# board.net
KiCad netlist of a schematic drawn in EAGLE
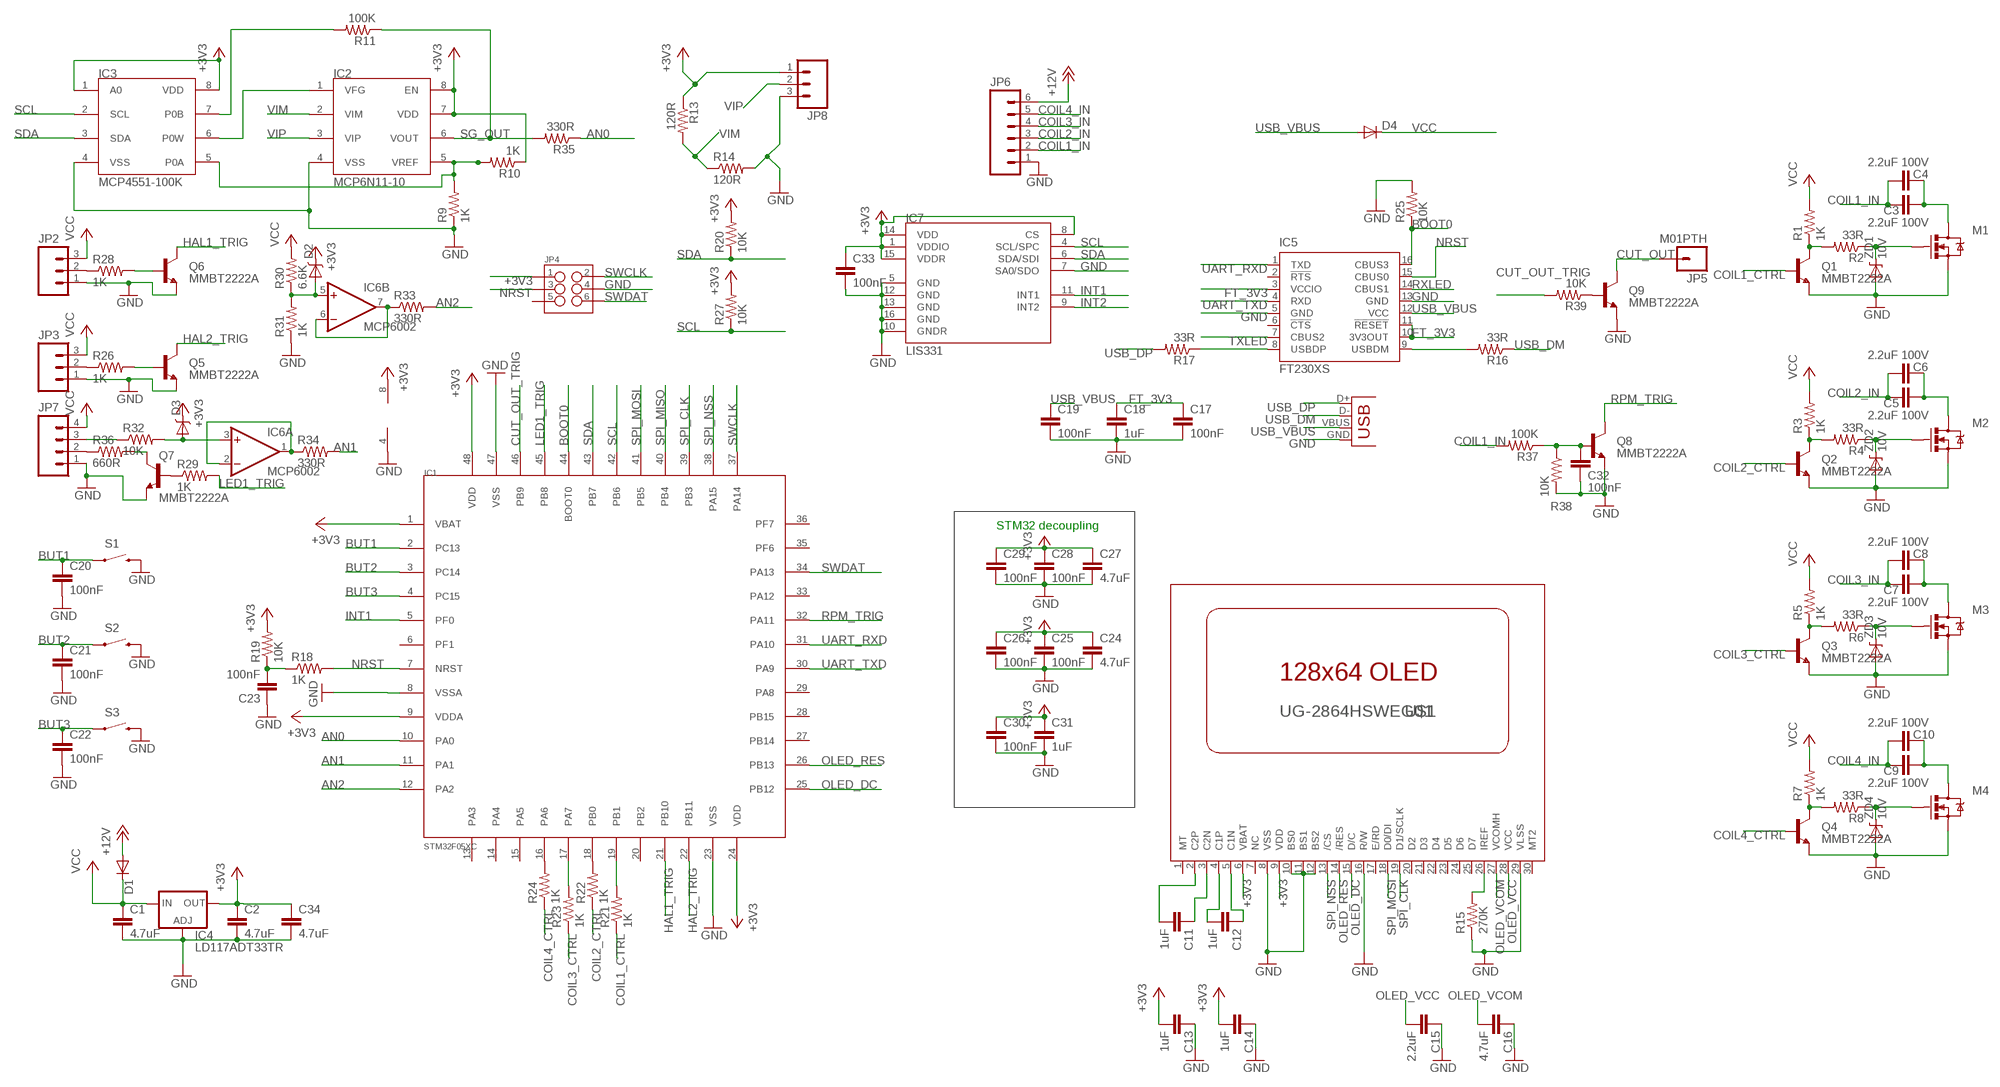
[diagram p0: schematic, sheet 1]

(export (version "E")
  (design (tool "Eeschema 10.0.6"))
  (components
    (comp (ref "C1")
      (value "4.7uF")
      (footprint "eagle-import:0603-CAP")
      (libsource (lib "eagle-import") (part "SparkFun-Passives_CAP0603-CAP"))
    )
    (comp (ref "C2")
      (value "4.7uF")
      (footprint "eagle-import:0603-CAP")
      (libsource (lib "eagle-import") (part "SparkFun-Passives_CAP0603-CAP"))
    )
    (comp (ref "C3")
      (value "2.2uF 100V")
      (footprint "eagle-import:1206")
      (libsource (lib "eagle-import") (part "2.2UF-CERCAP-10009"))
    )
    (comp (ref "C4")
      (value "2.2uF 100V")
      (footprint "eagle-import:1206")
      (libsource (lib "eagle-import") (part "2.2UF-CERCAP-10009"))
    )
    (comp (ref "C5")
      (value "2.2uF 100V")
      (footprint "eagle-import:1206")
      (libsource (lib "eagle-import") (part "2.2UF-CERCAP-10009"))
    )
    (comp (ref "C6")
      (value "2.2uF 100V")
      (footprint "eagle-import:1206")
      (libsource (lib "eagle-import") (part "2.2UF-CERCAP-10009"))
    )
    (comp (ref "C7")
      (value "2.2uF 100V")
      (footprint "eagle-import:1206")
      (libsource (lib "eagle-import") (part "2.2UF-CERCAP-10009"))
    )
    (comp (ref "C8")
      (value "2.2uF 100V")
      (footprint "eagle-import:1206")
      (libsource (lib "eagle-import") (part "2.2UF-CERCAP-10009"))
    )
    (comp (ref "C9")
      (value "2.2uF 100V")
      (footprint "eagle-import:1206")
      (libsource (lib "eagle-import") (part "2.2UF-CERCAP-10009"))
    )
    (comp (ref "C10")
      (value "2.2uF 100V")
      (footprint "eagle-import:1206")
      (libsource (lib "eagle-import") (part "2.2UF-CERCAP-10009"))
    )
    (comp (ref "C11")
      (value "1uF")
      (footprint "eagle-import:0603-CAP")
      (libsource (lib "eagle-import") (part "CAP0603-CAP"))
    )
    (comp (ref "C12")
      (value "1uF")
      (footprint "eagle-import:0603-CAP")
      (libsource (lib "eagle-import") (part "CAP0603-CAP"))
    )
    (comp (ref "C13")
      (value "1uF")
      (footprint "eagle-import:0603-CAP")
      (libsource (lib "eagle-import") (part "CAP0603-CAP"))
    )
    (comp (ref "C14")
      (value "1uF")
      (footprint "eagle-import:0603-CAP")
      (libsource (lib "eagle-import") (part "CAP0603-CAP"))
    )
    (comp (ref "C15")
      (value "2.2uF")
      (footprint "eagle-import:0603-CAP")
      (libsource (lib "eagle-import") (part "CAP0603-CAP"))
    )
    (comp (ref "C16")
      (value "4.7uF")
      (footprint "eagle-import:0603-CAP")
      (libsource (lib "eagle-import") (part "CAP0603-CAP"))
    )
    (comp (ref "C17")
      (value "100nF")
      (footprint "eagle-import:0603-CAP")
      (libsource (lib "eagle-import") (part "CAP0603-CAP"))
    )
    (comp (ref "C18")
      (value "1uF")
      (footprint "eagle-import:0603-CAP")
      (libsource (lib "eagle-import") (part "CAP0603-CAP"))
    )
    (comp (ref "C19")
      (value "100nF")
      (footprint "eagle-import:0603-CAP")
      (libsource (lib "eagle-import") (part "CAP0603-CAP"))
    )
    (comp (ref "C20")
      (value "100nF")
      (footprint "eagle-import:0603-CAP")
      (libsource (lib "eagle-import") (part "CAP0603-CAP"))
    )
    (comp (ref "C21")
      (value "100nF")
      (footprint "eagle-import:0603-CAP")
      (libsource (lib "eagle-import") (part "CAP0603-CAP"))
    )
    (comp (ref "C22")
      (value "100nF")
      (footprint "eagle-import:0603-CAP")
      (libsource (lib "eagle-import") (part "CAP0603-CAP"))
    )
    (comp (ref "C23")
      (value "100nF")
      (footprint "eagle-import:0603-CAP")
      (libsource (lib "eagle-import") (part "CAP0603-CAP"))
    )
    (comp (ref "C24")
      (value "4.7uF")
      (footprint "eagle-import:0603-CAP")
      (libsource (lib "eagle-import") (part "SparkFun-Passives_CAP0603-CAP"))
    )
    (comp (ref "C25")
      (value "100nF")
      (footprint "eagle-import:0603-CAP")
      (libsource (lib "eagle-import") (part "CAP0603-CAP"))
    )
    (comp (ref "C26")
      (value "100nF")
      (footprint "eagle-import:0603-CAP")
      (libsource (lib "eagle-import") (part "CAP0603-CAP"))
    )
    (comp (ref "C27")
      (value "4.7uF")
      (footprint "eagle-import:0603-CAP")
      (libsource (lib "eagle-import") (part "SparkFun-Passives_CAP0603-CAP"))
    )
    (comp (ref "C28")
      (value "100nF")
      (footprint "eagle-import:0603-CAP")
      (libsource (lib "eagle-import") (part "CAP0603-CAP"))
    )
    (comp (ref "C29")
      (value "100nF")
      (footprint "eagle-import:0603-CAP")
      (libsource (lib "eagle-import") (part "CAP0603-CAP"))
    )
    (comp (ref "C30")
      (value "100nF")
      (footprint "eagle-import:0603-CAP")
      (libsource (lib "eagle-import") (part "CAP0603-CAP"))
    )
    (comp (ref "C31")
      (value "1uF")
      (footprint "eagle-import:0603-CAP")
      (libsource (lib "eagle-import") (part "CAP0603-CAP"))
    )
    (comp (ref "C32")
      (value "100nF")
      (footprint "eagle-import:0603-CAP")
      (libsource (lib "eagle-import") (part "CAP0603-CAP"))
    )
    (comp (ref "C33")
      (value "100nF")
      (footprint "eagle-import:0603-CAP")
      (libsource (lib "eagle-import") (part "CAP0603-CAP"))
    )
    (comp (ref "C34")
      (value "4.7uF")
      (footprint "eagle-import:0603-CAP")
      (libsource (lib "eagle-import") (part "SparkFun-Passives_CAP0603-CAP"))
    )
    (comp (ref "D1")
      (value "DIODESMA")
      (footprint "eagle-import:SMA-DIODE")
      (libsource (lib "eagle-import") (part "DIODESMA"))
    )
    (comp (ref "D2")
      (value "BAT20JFILM")
      (footprint "eagle-import:SOD-323")
      (libsource (lib "eagle-import") (part "BAT20JFILM"))
    )
    (comp (ref "D3")
      (value "BAT20JFILM")
      (footprint "eagle-import:SOD-323")
      (libsource (lib "eagle-import") (part "BAT20JFILM"))
    )
    (comp (ref "D4")
      (value "DIODESMA")
      (footprint "eagle-import:SMA-DIODE")
      (libsource (lib "eagle-import") (part "DIODESMA"))
    )
    (comp (ref "IC1")
      (value "STM32F05XC")
      (footprint "eagle-import:LQFP-48")
      (libsource (lib "eagle-import") (part "STM32F05XC"))
    )
    (comp (ref "IC2")
      (value "MCP6N11-10")
      (footprint "eagle-import:SO08")
      (libsource (lib "eagle-import") (part "MCP6N11"))
    )
    (comp (ref "IC3")
      (value "MCP4551-100K")
      (footprint "eagle-import:MSOP-8")
      (libsource (lib "eagle-import") (part "MCP45X1"))
    )
    (comp (ref "IC4")
      (value "LD117ADT33TR")
      (footprint "eagle-import:DPACK")
      (libsource (lib "eagle-import") (part "LD117A?DT33TR"))
    )
    (comp (ref "IC5")
      (value "FT230XS")
      (footprint "eagle-import:SSOP16")
      (libsource (lib "eagle-import") (part "FT230XS"))
    )
    (comp (ref "IC6")
      (value "MCP6002")
      (footprint "eagle-import:SO08")
      (libsource (lib "eagle-import") (part "TL072D"))
    )
    (comp (ref "IC7")
      (value "LIS331")
      (footprint "eagle-import:LGA16-3MM")
      (libsource (lib "eagle-import") (part "LIS331"))
    )
    (comp (ref "JP1")
      (value "USBSMD")
      (footprint "eagle-import:USB-MINIB")
      (libsource (lib "eagle-import") (part "USBSMD"))
    )
    (comp (ref "JP2")
      (value "M03PTH")
      (footprint "eagle-import:1X03")
      (libsource (lib "eagle-import") (part "M03PTH"))
    )
    (comp (ref "JP3")
      (value "M03PTH")
      (footprint "eagle-import:1X03")
      (libsource (lib "eagle-import") (part "M03PTH"))
    )
    (comp (ref "JP4")
      (value "M03X22X3_SILK_SM")
      (footprint "eagle-import:2X3")
      (libsource (lib "eagle-import") (part "M03X22X3_SILK_SM"))
    )
    (comp (ref "JP5")
      (value "M01PTH")
      (footprint "eagle-import:1X01")
      (libsource (lib "eagle-import") (part "M01PTH"))
    )
    (comp (ref "JP6")
      (value "M063.5MM-6")
      (footprint "eagle-import:SCREWTERMINAL-3.5MM-6")
      (libsource (lib "eagle-import") (part "M063.5MM-6"))
    )
    (comp (ref "JP7")
      (value "M04PTH")
      (footprint "eagle-import:1X04")
      (libsource (lib "eagle-import") (part "M04PTH"))
    )
    (comp (ref "JP8")
      (value "M03PTH")
      (footprint "eagle-import:1X03")
      (libsource (lib "eagle-import") (part "M03PTH"))
    )
    (comp (ref "M1")
      (value "MOSFET-NCHANNELFDD8580")
      (footprint "eagle-import:DPAK")
      (libsource (lib "eagle-import") (part "MOSFET-NCHANNELFDD8580"))
    )
    (comp (ref "M2")
      (value "MOSFET-NCHANNELFDD8580")
      (footprint "eagle-import:DPAK")
      (libsource (lib "eagle-import") (part "MOSFET-NCHANNELFDD8580"))
    )
    (comp (ref "M3")
      (value "MOSFET-NCHANNELFDD8580")
      (footprint "eagle-import:DPAK")
      (libsource (lib "eagle-import") (part "MOSFET-NCHANNELFDD8580"))
    )
    (comp (ref "M4")
      (value "MOSFET-NCHANNELFDD8580")
      (footprint "eagle-import:DPAK")
      (libsource (lib "eagle-import") (part "MOSFET-NCHANNELFDD8580"))
    )
    (comp (ref "Q1")
      (value "MMBT2222A")
      (footprint "eagle-import:SOT23")
      (libsource (lib "eagle-import") (part "TRANSISTOR_NPNMMBT2222A"))
    )
    (comp (ref "Q2")
      (value "MMBT2222A")
      (footprint "eagle-import:SOT23")
      (libsource (lib "eagle-import") (part "TRANSISTOR_NPNMMBT2222A"))
    )
    (comp (ref "Q3")
      (value "MMBT2222A")
      (footprint "eagle-import:SOT23")
      (libsource (lib "eagle-import") (part "TRANSISTOR_NPNMMBT2222A"))
    )
    (comp (ref "Q4")
      (value "MMBT2222A")
      (footprint "eagle-import:SOT23")
      (libsource (lib "eagle-import") (part "TRANSISTOR_NPNMMBT2222A"))
    )
    (comp (ref "Q5")
      (value "MMBT2222A")
      (footprint "eagle-import:SOT23")
      (fields (field (name "PROD_ID") "TRANS-08049"))
      (libsource (lib "eagle-import") (part "TRANSISTOR_NPNMMBT2222A"))
    )
    (comp (ref "Q6")
      (value "MMBT2222A")
      (footprint "eagle-import:SOT23")
      (fields (field (name "PROD_ID") "TRANS-08049"))
      (libsource (lib "eagle-import") (part "TRANSISTOR_NPNMMBT2222A"))
    )
    (comp (ref "Q7")
      (value "MMBT2222A")
      (footprint "eagle-import:SOT23")
      (libsource (lib "eagle-import") (part "TRANSISTOR_NPNMMBT2222A"))
    )
    (comp (ref "Q8")
      (value "MMBT2222A")
      (footprint "eagle-import:SOT23")
      (libsource (lib "eagle-import") (part "TRANSISTOR_NPNMMBT2222A"))
    )
    (comp (ref "Q9")
      (value "MMBT2222A")
      (footprint "eagle-import:SOT23")
      (libsource (lib "eagle-import") (part "TRANSISTOR_NPNMMBT2222A"))
    )
    (comp (ref "R1")
      (value "1K")
      (footprint "eagle-import:0603-RES")
      (libsource (lib "eagle-import") (part "RESISTOR0603-RES"))
    )
    (comp (ref "R2")
      (value "33R")
      (footprint "eagle-import:0603-RES")
      (libsource (lib "eagle-import") (part "RESISTOR0603-RES"))
    )
    (comp (ref "R3")
      (value "1K")
      (footprint "eagle-import:0603-RES")
      (libsource (lib "eagle-import") (part "RESISTOR0603-RES"))
    )
    (comp (ref "R4")
      (value "33R")
      (footprint "eagle-import:0603-RES")
      (libsource (lib "eagle-import") (part "RESISTOR0603-RES"))
    )
    (comp (ref "R5")
      (value "1K")
      (footprint "eagle-import:0603-RES")
      (libsource (lib "eagle-import") (part "RESISTOR0603-RES"))
    )
    (comp (ref "R6")
      (value "33R")
      (footprint "eagle-import:0603-RES")
      (libsource (lib "eagle-import") (part "RESISTOR0603-RES"))
    )
    (comp (ref "R7")
      (value "1K")
      (footprint "eagle-import:0603-RES")
      (libsource (lib "eagle-import") (part "RESISTOR0603-RES"))
    )
    (comp (ref "R8")
      (value "33R")
      (footprint "eagle-import:0603-RES")
      (libsource (lib "eagle-import") (part "RESISTOR0603-RES"))
    )
    (comp (ref "R9")
      (value "1K")
      (footprint "eagle-import:0603-RES")
      (libsource (lib "eagle-import") (part "RESISTOR0603-RES"))
    )
    (comp (ref "R10")
      (value "1K")
      (footprint "eagle-import:0603-RES")
      (libsource (lib "eagle-import") (part "RESISTOR0603-RES"))
    )
    (comp (ref "R11")
      (value "100K")
      (footprint "eagle-import:0603-RES")
      (libsource (lib "eagle-import") (part "RESISTOR0603-RES"))
    )
    (comp (ref "R13")
      (value "120R")
      (footprint "eagle-import:0603-RES")
      (libsource (lib "eagle-import") (part "RESISTOR0603-RES"))
    )
    (comp (ref "R14")
      (value "120R")
      (footprint "eagle-import:0603-RES")
      (libsource (lib "eagle-import") (part "RESISTOR0603-RES"))
    )
    (comp (ref "R15")
      (value "270K")
      (footprint "eagle-import:0603-RES")
      (libsource (lib "eagle-import") (part "RESISTOR0603"))
    )
    (comp (ref "R16")
      (value "33R")
      (footprint "eagle-import:0603-RES")
      (libsource (lib "eagle-import") (part "RESISTOR0603-RES"))
    )
    (comp (ref "R17")
      (value "33R")
      (footprint "eagle-import:0603-RES")
      (libsource (lib "eagle-import") (part "RESISTOR0603-RES"))
    )
    (comp (ref "R18")
      (value "1K")
      (footprint "eagle-import:0603-RES")
      (libsource (lib "eagle-import") (part "RESISTOR0603-RES"))
    )
    (comp (ref "R19")
      (value "10K")
      (footprint "eagle-import:0603-RES")
      (libsource (lib "eagle-import") (part "RESISTOR0603-RES"))
    )
    (comp (ref "R20")
      (value "10K")
      (footprint "eagle-import:0603-RES")
      (libsource (lib "eagle-import") (part "RESISTOR0603-RES"))
    )
    (comp (ref "R21")
      (value "1K")
      (footprint "eagle-import:0603-RES")
      (libsource (lib "eagle-import") (part "RESISTOR0603-RES"))
    )
    (comp (ref "R22")
      (value "1K")
      (footprint "eagle-import:0603-RES")
      (libsource (lib "eagle-import") (part "RESISTOR0603-RES"))
    )
    (comp (ref "R23")
      (value "1K")
      (footprint "eagle-import:0603-RES")
      (libsource (lib "eagle-import") (part "RESISTOR0603-RES"))
    )
    (comp (ref "R24")
      (value "1K")
      (footprint "eagle-import:0603-RES")
      (libsource (lib "eagle-import") (part "RESISTOR0603-RES"))
    )
    (comp (ref "R25")
      (value "10K")
      (footprint "eagle-import:0603-RES")
      (libsource (lib "eagle-import") (part "RESISTOR0603-RES"))
    )
    (comp (ref "R26")
      (value "1K")
      (footprint "eagle-import:0603-RES")
      (libsource (lib "eagle-import") (part "RESISTOR0603-RES"))
    )
    (comp (ref "R27")
      (value "10K")
      (footprint "eagle-import:0603-RES")
      (libsource (lib "eagle-import") (part "RESISTOR0603-RES"))
    )
    (comp (ref "R28")
      (value "1K")
      (footprint "eagle-import:0603-RES")
      (libsource (lib "eagle-import") (part "RESISTOR0603-RES"))
    )
    (comp (ref "R29")
      (value "1K")
      (footprint "eagle-import:0603-RES")
      (libsource (lib "eagle-import") (part "RESISTOR0603-RES"))
    )
    (comp (ref "R30")
      (value "6.6K")
      (footprint "eagle-import:0603-RES")
      (libsource (lib "eagle-import") (part "RESISTOR0603-RES"))
    )
    (comp (ref "R31")
      (value "1K")
      (footprint "eagle-import:0603-RES")
      (libsource (lib "eagle-import") (part "RESISTOR0603-RES"))
    )
    (comp (ref "R32")
      (value "10K")
      (footprint "eagle-import:0603-RES")
      (libsource (lib "eagle-import") (part "RESISTOR0603-RES"))
    )
    (comp (ref "R33")
      (value "330R")
      (footprint "eagle-import:0603-RES")
      (libsource (lib "eagle-import") (part "RESISTOR0603-RES"))
    )
    (comp (ref "R34")
      (value "330R")
      (footprint "eagle-import:0603-RES")
      (libsource (lib "eagle-import") (part "RESISTOR0603-RES"))
    )
    (comp (ref "R35")
      (value "330R")
      (footprint "eagle-import:0603-RES")
      (libsource (lib "eagle-import") (part "RESISTOR0603-RES"))
    )
    (comp (ref "R36")
      (value "660R")
      (footprint "eagle-import:1206")
      (libsource (lib "eagle-import") (part "RESISTOR1206"))
    )
    (comp (ref "R37")
      (value "100K")
      (footprint "eagle-import:1206")
      (libsource (lib "eagle-import") (part "RESISTOR1206"))
    )
    (comp (ref "R38")
      (value "10K")
      (footprint "eagle-import:0603-RES")
      (libsource (lib "eagle-import") (part "RESISTOR0603-RES"))
    )
    (comp (ref "R39")
      (value "10K")
      (footprint "eagle-import:0603-RES")
      (libsource (lib "eagle-import") (part "RESISTOR0603-RES"))
    )
    (comp (ref "S1")
      (value "SWITCH-MOMENTARY-2")
      (footprint "eagle-import:TACTILE_SWITCH_TALL")
      (libsource (lib "eagle-import") (part "SWITCH-MOMENTARY-2"))
    )
    (comp (ref "S2")
      (value "SWITCH-MOMENTARY-2")
      (footprint "eagle-import:TACTILE_SWITCH_TALL")
      (libsource (lib "eagle-import") (part "SWITCH-MOMENTARY-2"))
    )
    (comp (ref "S3")
      (value "SWITCH-MOMENTARY-2")
      (footprint "eagle-import:TACTILE_SWITCH_TALL")
      (libsource (lib "eagle-import") (part "SWITCH-MOMENTARY-2"))
    )
    (comp (ref "U$1")
      (value "UG-2864HSWEG01")
      (footprint "eagle-import:1X30-0.7MM")
      (libsource (lib "eagle-import") (part "UG-2864HSWEG01"))
    )
    (comp (ref "ZD1")
      (value "10V")
      (footprint "eagle-import:SOD-323")
      (libsource (lib "eagle-import") (part "DIODE-ZENER-BZT52"))
    )
    (comp (ref "ZD2")
      (value "10V")
      (footprint "eagle-import:SOD-323")
      (libsource (lib "eagle-import") (part "DIODE-ZENER-BZT52"))
    )
    (comp (ref "ZD3")
      (value "10V")
      (footprint "eagle-import:SOD-323")
      (libsource (lib "eagle-import") (part "DIODE-ZENER-BZT52"))
    )
    (comp (ref "ZD4")
      (value "10V")
      (footprint "eagle-import:SOD-323")
      (libsource (lib "eagle-import") (part "DIODE-ZENER-BZT52"))
    )
  )
  (nets
    (net (code "1") (name "+3V3") (class "Default")
      (node (ref "C13") (pin "2") (pinfunction "2_2") (pintype "passive"))
      (node (ref "C14") (pin "2") (pinfunction "2_2") (pintype "passive"))
      (node (ref "C2") (pin "1") (pinfunction "1_1") (pintype "passive"))
      (node (ref "C24") (pin "1") (pinfunction "1_1") (pintype "passive"))
      (node (ref "C25") (pin "1") (pinfunction "1_1") (pintype "passive"))
      (node (ref "C26") (pin "1") (pinfunction "1_1") (pintype "passive"))
      (node (ref "C27") (pin "1") (pinfunction "1_1") (pintype "passive"))
      (node (ref "C28") (pin "1") (pinfunction "1_1") (pintype "passive"))
      (node (ref "C29") (pin "1") (pinfunction "1_1") (pintype "passive"))
      (node (ref "C30") (pin "1") (pinfunction "1_1") (pintype "passive"))
      (node (ref "C31") (pin "1") (pinfunction "1_1") (pintype "passive"))
      (node (ref "C33") (pin "1") (pinfunction "1_1") (pintype "passive"))
      (node (ref "C34") (pin "1") (pinfunction "1_1") (pintype "passive"))
      (node (ref "D2") (pin "1") (pinfunction "C_1") (pintype "passive"))
      (node (ref "D3") (pin "1") (pinfunction "C_1") (pintype "passive"))
      (node (ref "IC1") (pin "1") (pinfunction "VBAT_1") (pintype "bidirectional"))
      (node (ref "IC1") (pin "24") (pinfunction "VDD_24") (pintype "bidirectional"))
      (node (ref "IC1") (pin "48") (pinfunction "VDD_48") (pintype "bidirectional"))
      (node (ref "IC1") (pin "9") (pinfunction "VDDA_9") (pintype "bidirectional"))
      (node (ref "IC2") (pin "7") (pinfunction "VDD_7") (pintype "bidirectional"))
      (node (ref "IC2") (pin "8") (pinfunction "EN_8") (pintype "bidirectional"))
      (node (ref "IC3") (pin "1") (pinfunction "A0_1") (pintype "bidirectional"))
      (node (ref "IC3") (pin "8") (pinfunction "VDD_8") (pintype "bidirectional"))
      (node (ref "IC4") (pin "4") (pinfunction "OUT_4") (pintype "passive"))
      (node (ref "IC6") (pin "8") (pinfunction "V+_8") (pintype "power_in"))
      (node (ref "IC7") (pin "1") (pinfunction "VDDIO_1") (pintype "bidirectional"))
      (node (ref "IC7") (pin "14") (pinfunction "VDD_14") (pintype "bidirectional"))
      (node (ref "IC7") (pin "15") (pinfunction "VDDR_15") (pintype "bidirectional"))
      (node (ref "IC7") (pin "8") (pinfunction "CS_8") (pintype "bidirectional"))
      (node (ref "JP4") (pin "1") (pinfunction "1_1") (pintype "bidirectional"))
      (node (ref "JP8") (pin "1") (pinfunction "1_1") (pintype "passive"))
      (node (ref "R10") (pin "1") (pinfunction "1_1") (pintype "passive"))
      (node (ref "R13") (pin "1") (pinfunction "1_1") (pintype "passive"))
      (node (ref "R19") (pin "2") (pinfunction "2_2") (pintype "passive"))
      (node (ref "R20") (pin "2") (pinfunction "2_2") (pintype "passive"))
      (node (ref "R27") (pin "2") (pinfunction "2_2") (pintype "passive"))
      (node (ref "U$1") (pin "6") (pinfunction "VBAT_6") (pintype "input"))
      (node (ref "U$1") (pin "9") (pinfunction "VDD_9") (pintype "power_in"))
    )
    (net (code "2") (name "+12V") (class "Default")
      (node (ref "D1") (pin "A") (pinfunction "A_A") (pintype "passive"))
      (node (ref "JP6") (pin "6") (pinfunction "6_6") (pintype "passive"))
    )
    (net (code "3") (name "/AN0") (class "Default")
      (node (ref "IC1") (pin "10") (pinfunction "PA0_10") (pintype "bidirectional"))
      (node (ref "R35") (pin "1") (pinfunction "1_1") (pintype "passive"))
    )
    (net (code "4") (name "/AN1") (class "Default")
      (node (ref "IC1") (pin "11") (pinfunction "PA1_11") (pintype "bidirectional"))
      (node (ref "R34") (pin "2") (pinfunction "2_2") (pintype "passive"))
    )
    (net (code "5") (name "/AN2") (class "Default")
      (node (ref "IC1") (pin "12") (pinfunction "PA2_12") (pintype "bidirectional"))
      (node (ref "R33") (pin "2") (pinfunction "2_2") (pintype "passive"))
    )
    (net (code "6") (name "/BOOT0") (class "Default")
      (node (ref "IC1") (pin "44") (pinfunction "BOOT0_44") (pintype "bidirectional"))
      (node (ref "IC5") (pin "16") (pinfunction "CBUS3_16") (pintype "bidirectional"))
      (node (ref "R25") (pin "1") (pinfunction "1_1") (pintype "passive"))
    )
    (net (code "7") (name "/BUT1") (class "Default")
      (node (ref "C20") (pin "1") (pinfunction "1_1") (pintype "passive"))
      (node (ref "IC1") (pin "2") (pinfunction "PC13_2") (pintype "bidirectional"))
      (node (ref "S1") (pin "A2") (pinfunction "1_A2") (pintype "passive"))
    )
    (net (code "8") (name "/BUT2") (class "Default")
      (node (ref "C21") (pin "1") (pinfunction "1_1") (pintype "passive"))
      (node (ref "IC1") (pin "3") (pinfunction "PC14_3") (pintype "bidirectional"))
      (node (ref "S2") (pin "A2") (pinfunction "1_A2") (pintype "passive"))
    )
    (net (code "9") (name "/BUT3") (class "Default")
      (node (ref "C22") (pin "1") (pinfunction "1_1") (pintype "passive"))
      (node (ref "IC1") (pin "4") (pinfunction "PC15_4") (pintype "bidirectional"))
      (node (ref "S3") (pin "A2") (pinfunction "1_A2") (pintype "passive"))
    )
    (net (code "10") (name "/COIL1_CTRL") (class "Default")
      (node (ref "Q1") (pin "1") (pinfunction "B_1") (pintype "passive"))
      (node (ref "R21") (pin "1") (pinfunction "1_1") (pintype "passive"))
    )
    (net (code "11") (name "/COIL1_IN") (class "Default")
      (node (ref "C3") (pin "1") (pinfunction "1_1") (pintype "passive"))
      (node (ref "C4") (pin "1") (pinfunction "1_1") (pintype "passive"))
      (node (ref "JP6") (pin "2") (pinfunction "2_2") (pintype "passive"))
      (node (ref "R37") (pin "2") (pinfunction "2_2") (pintype "passive"))
    )
    (net (code "12") (name "/COIL2_CTRL") (class "Default")
      (node (ref "Q2") (pin "1") (pinfunction "B_1") (pintype "passive"))
      (node (ref "R22") (pin "1") (pinfunction "1_1") (pintype "passive"))
    )
    (net (code "13") (name "/COIL2_IN") (class "Default")
      (node (ref "C5") (pin "1") (pinfunction "1_1") (pintype "passive"))
      (node (ref "C6") (pin "1") (pinfunction "1_1") (pintype "passive"))
      (node (ref "JP6") (pin "3") (pinfunction "3_3") (pintype "passive"))
    )
    (net (code "14") (name "/COIL3_CTRL") (class "Default")
      (node (ref "Q3") (pin "1") (pinfunction "B_1") (pintype "passive"))
      (node (ref "R23") (pin "1") (pinfunction "1_1") (pintype "passive"))
    )
    (net (code "15") (name "/COIL3_IN") (class "Default")
      (node (ref "C7") (pin "1") (pinfunction "1_1") (pintype "passive"))
      (node (ref "C8") (pin "1") (pinfunction "1_1") (pintype "passive"))
      (node (ref "JP6") (pin "4") (pinfunction "4_4") (pintype "passive"))
    )
    (net (code "16") (name "/COIL4_CTRL") (class "Default")
      (node (ref "Q4") (pin "1") (pinfunction "B_1") (pintype "passive"))
      (node (ref "R24") (pin "1") (pinfunction "1_1") (pintype "passive"))
    )
    (net (code "17") (name "/COIL4_IN") (class "Default")
      (node (ref "C10") (pin "1") (pinfunction "1_1") (pintype "passive"))
      (node (ref "C9") (pin "1") (pinfunction "1_1") (pintype "passive"))
      (node (ref "JP6") (pin "5") (pinfunction "5_5") (pintype "passive"))
    )
    (net (code "18") (name "/CUT_OUT") (class "Default")
      (node (ref "JP5") (pin "1") (pinfunction "1_1") (pintype "passive"))
      (node (ref "Q9") (pin "3") (pinfunction "C_3") (pintype "passive"))
    )
    (net (code "19") (name "/CUT_OUT_TRIG") (class "Default")
      (node (ref "IC1") (pin "46") (pinfunction "PB9_46") (pintype "bidirectional"))
      (node (ref "R39") (pin "2") (pinfunction "2_2") (pintype "passive"))
    )
    (net (code "20") (name "/FT_3V3") (class "Default")
      (node (ref "C17") (pin "1") (pinfunction "1_1") (pintype "passive"))
      (node (ref "C18") (pin "1") (pinfunction "1_1") (pintype "passive"))
      (node (ref "IC5") (pin "10") (pinfunction "3V3OUT_10") (pintype "output"))
      (node (ref "IC5") (pin "11") (pinfunction "~{RESET}_11") (pintype "input"))
      (node (ref "IC5") (pin "3") (pinfunction "VCCIO_3") (pintype "power_in"))
    )
    (net (code "21") (name "/HAL1_TRIG") (class "Default")
      (node (ref "IC1") (pin "21") (pinfunction "PB10_21") (pintype "bidirectional"))
      (node (ref "Q6") (pin "3") (pinfunction "C_3") (pintype "passive"))
    )
    (net (code "22") (name "/HAL2_TRIG") (class "Default")
      (node (ref "IC1") (pin "22") (pinfunction "PB11_22") (pintype "bidirectional"))
      (node (ref "Q5") (pin "3") (pinfunction "C_3") (pintype "passive"))
    )
    (net (code "23") (name "/INT1") (class "Default")
      (node (ref "IC1") (pin "5") (pinfunction "PF0_5") (pintype "bidirectional"))
      (node (ref "IC7") (pin "11") (pinfunction "INT1_11") (pintype "bidirectional"))
    )
    (net (code "24") (name "/INT2") (class "Default")
      (node (ref "IC7") (pin "9") (pinfunction "INT2_9") (pintype "bidirectional"))
    )
    (net (code "25") (name "/LED1_TRIG") (class "Default")
      (node (ref "IC1") (pin "45") (pinfunction "PB8_45") (pintype "bidirectional"))
      (node (ref "R29") (pin "2") (pinfunction "2_2") (pintype "passive"))
    )
    (net (code "26") (name "/NRST") (class "Default")
      (node (ref "IC1") (pin "7") (pinfunction "NRST_7") (pintype "bidirectional"))
      (node (ref "IC5") (pin "15") (pinfunction "CBUS0_15") (pintype "bidirectional"))
      (node (ref "JP4") (pin "3") (pinfunction "3_3") (pintype "bidirectional"))
      (node (ref "R18") (pin "2") (pinfunction "2_2") (pintype "passive"))
    )
    (net (code "27") (name "/OLED_DC") (class "Default")
      (node (ref "IC1") (pin "25") (pinfunction "PB12_25") (pintype "bidirectional"))
      (node (ref "U$1") (pin "15") (pinfunction "D/C_15") (pintype "input"))
    )
    (net (code "28") (name "/OLED_RES") (class "Default")
      (node (ref "IC1") (pin "26") (pinfunction "PB13_26") (pintype "bidirectional"))
      (node (ref "U$1") (pin "14") (pinfunction "/RES_14") (pintype "input"))
    )
    (net (code "29") (name "/OLED_VCC") (class "Default")
      (node (ref "C15") (pin "2") (pinfunction "2_2") (pintype "passive"))
      (node (ref "U$1") (pin "28") (pinfunction "VCC_28") (pintype "power_in"))
    )
    (net (code "30") (name "/OLED_VCOM") (class "Default")
      (node (ref "C16") (pin "2") (pinfunction "2_2") (pintype "passive"))
      (node (ref "U$1") (pin "27") (pinfunction "VCOMH_27") (pintype "output"))
    )
    (net (code "31") (name "/RPM_TRIG") (class "Default")
      (node (ref "IC1") (pin "32") (pinfunction "PA11_32") (pintype "bidirectional"))
      (node (ref "Q8") (pin "3") (pinfunction "C_3") (pintype "passive"))
    )
    (net (code "32") (name "/RXLED") (class "Default")
      (node (ref "IC5") (pin "14") (pinfunction "CBUS1_14") (pintype "bidirectional"))
    )
    (net (code "33") (name "/SCL") (class "Default")
      (node (ref "IC1") (pin "42") (pinfunction "PB6_42") (pintype "bidirectional"))
      (node (ref "IC3") (pin "2") (pinfunction "SCL_2") (pintype "bidirectional"))
      (node (ref "IC7") (pin "4") (pinfunction "SCL/SPC_4") (pintype "bidirectional"))
      (node (ref "R27") (pin "1") (pinfunction "1_1") (pintype "passive"))
    )
    (net (code "34") (name "/SDA") (class "Default")
      (node (ref "IC1") (pin "43") (pinfunction "PB7_43") (pintype "bidirectional"))
      (node (ref "IC3") (pin "3") (pinfunction "SDA_3") (pintype "bidirectional"))
      (node (ref "IC7") (pin "6") (pinfunction "SDA/SDI_6") (pintype "bidirectional"))
      (node (ref "R20") (pin "1") (pinfunction "1_1") (pintype "passive"))
    )
    (net (code "35") (name "/SG_OUT") (class "Default")
      (node (ref "IC2") (pin "6") (pinfunction "VOUT_6") (pintype "bidirectional"))
      (node (ref "R11") (pin "1") (pinfunction "1_1") (pintype "passive"))
      (node (ref "R35") (pin "2") (pinfunction "2_2") (pintype "passive"))
    )
    (net (code "36") (name "/SPI_CLK") (class "Default")
      (node (ref "IC1") (pin "39") (pinfunction "PB3_39") (pintype "bidirectional"))
      (node (ref "U$1") (pin "19") (pinfunction "D1/SCLK_19") (pintype "bidirectional"))
    )
    (net (code "37") (name "/SPI_MISO") (class "Default")
      (node (ref "IC1") (pin "40") (pinfunction "PB4_40") (pintype "bidirectional"))
    )
    (net (code "38") (name "/SPI_MOSI") (class "Default")
      (node (ref "IC1") (pin "41") (pinfunction "PB5_41") (pintype "bidirectional"))
      (node (ref "U$1") (pin "18") (pinfunction "D0/DI_18") (pintype "bidirectional"))
    )
    (net (code "39") (name "/SPI_NSS") (class "Default")
      (node (ref "IC1") (pin "38") (pinfunction "PA15_38") (pintype "bidirectional"))
      (node (ref "U$1") (pin "13") (pinfunction "/CS_13") (pintype "input"))
    )
    (net (code "40") (name "/SWCLK") (class "Default")
      (node (ref "IC1") (pin "37") (pinfunction "PA14_37") (pintype "bidirectional"))
      (node (ref "JP4") (pin "2") (pinfunction "2_2") (pintype "bidirectional"))
    )
    (net (code "41") (name "/SWDAT") (class "Default")
      (node (ref "IC1") (pin "34") (pinfunction "PA13_34") (pintype "bidirectional"))
      (node (ref "JP4") (pin "6") (pinfunction "6_6") (pintype "bidirectional"))
    )
    (net (code "42") (name "/TXLED") (class "Default")
      (node (ref "IC5") (pin "7") (pinfunction "CBUS2_7") (pintype "bidirectional"))
    )
    (net (code "43") (name "/UART_RXD") (class "Default")
      (node (ref "IC1") (pin "31") (pinfunction "PA10_31") (pintype "bidirectional"))
      (node (ref "IC5") (pin "1") (pinfunction "TXD_1") (pintype "output"))
    )
    (net (code "44") (name "/UART_TXD") (class "Default")
      (node (ref "IC1") (pin "30") (pinfunction "PA9_30") (pintype "bidirectional"))
      (node (ref "IC5") (pin "4") (pinfunction "RXD_4") (pintype "input"))
    )
    (net (code "45") (name "/USB_DM") (class "Default")
      (node (ref "JP1") (pin "D-") (pinfunction "D-_D-") (pintype "bidirectional"))
      (node (ref "R16") (pin "1") (pinfunction "1_1") (pintype "passive"))
    )
    (net (code "46") (name "/USB_DP") (class "Default")
      (node (ref "JP1") (pin "D+") (pinfunction "D+_D+") (pintype "bidirectional"))
      (node (ref "R17") (pin "2") (pinfunction "2_2") (pintype "passive"))
    )
    (net (code "47") (name "/USB_VBUS") (class "Default")
      (node (ref "C19") (pin "1") (pinfunction "1_1") (pintype "passive"))
      (node (ref "D4") (pin "A") (pinfunction "A_A") (pintype "passive"))
      (node (ref "IC5") (pin "12") (pinfunction "VCC_12") (pintype "power_in"))
      (node (ref "JP1") (pin "VBUS") (pinfunction "VBUS_VBUS") (pintype "bidirectional"))
    )
    (net (code "48") (name "/VIM") (class "Default")
      (node (ref "IC2") (pin "2") (pinfunction "VIM_2") (pintype "bidirectional"))
      (node (ref "R13") (pin "2") (pinfunction "2_2") (pintype "passive"))
      (node (ref "R14") (pin "1") (pinfunction "1_1") (pintype "passive"))
    )
    (net (code "49") (name "/VIP") (class "Default")
      (node (ref "IC2") (pin "3") (pinfunction "VIP_3") (pintype "bidirectional"))
      (node (ref "JP8") (pin "2") (pinfunction "2_2") (pintype "passive"))
    )
    (net (code "50") (name "GND") (class "Default")
      (node (ref "C1") (pin "2") (pinfunction "2_2") (pintype "passive"))
      (node (ref "C13") (pin "1") (pinfunction "1_1") (pintype "passive"))
      (node (ref "C14") (pin "1") (pinfunction "1_1") (pintype "passive"))
      (node (ref "C15") (pin "1") (pinfunction "1_1") (pintype "passive"))
      (node (ref "C16") (pin "1") (pinfunction "1_1") (pintype "passive"))
      (node (ref "C17") (pin "2") (pinfunction "2_2") (pintype "passive"))
      (node (ref "C18") (pin "2") (pinfunction "2_2") (pintype "passive"))
      (node (ref "C19") (pin "2") (pinfunction "2_2") (pintype "passive"))
      (node (ref "C2") (pin "2") (pinfunction "2_2") (pintype "passive"))
      (node (ref "C20") (pin "2") (pinfunction "2_2") (pintype "passive"))
      (node (ref "C21") (pin "2") (pinfunction "2_2") (pintype "passive"))
      (node (ref "C22") (pin "2") (pinfunction "2_2") (pintype "passive"))
      (node (ref "C23") (pin "1") (pinfunction "1_1") (pintype "passive"))
      (node (ref "C24") (pin "2") (pinfunction "2_2") (pintype "passive"))
      (node (ref "C25") (pin "2") (pinfunction "2_2") (pintype "passive"))
      (node (ref "C26") (pin "2") (pinfunction "2_2") (pintype "passive"))
      (node (ref "C27") (pin "2") (pinfunction "2_2") (pintype "passive"))
      (node (ref "C28") (pin "2") (pinfunction "2_2") (pintype "passive"))
      (node (ref "C29") (pin "2") (pinfunction "2_2") (pintype "passive"))
      (node (ref "C30") (pin "2") (pinfunction "2_2") (pintype "passive"))
      (node (ref "C31") (pin "2") (pinfunction "2_2") (pintype "passive"))
      (node (ref "C32") (pin "2") (pinfunction "2_2") (pintype "passive"))
      (node (ref "C33") (pin "2") (pinfunction "2_2") (pintype "passive"))
      (node (ref "C34") (pin "2") (pinfunction "2_2") (pintype "passive"))
      (node (ref "IC1") (pin "23") (pinfunction "VSS_23") (pintype "bidirectional"))
      (node (ref "IC1") (pin "47") (pinfunction "VSS_47") (pintype "bidirectional"))
      (node (ref "IC1") (pin "8") (pinfunction "VSSA_8") (pintype "bidirectional"))
      (node (ref "IC2") (pin "4") (pinfunction "VSS_4") (pintype "bidirectional"))
      (node (ref "IC3") (pin "4") (pinfunction "VSS_4") (pintype "bidirectional"))
      (node (ref "IC4") (pin "1") (pinfunction "ADJ_1") (pintype "input"))
      (node (ref "IC5") (pin "13") (pinfunction "GND_13") (pintype "power_in"))
      (node (ref "IC5") (pin "5") (pinfunction "GND_5") (pintype "power_in"))
      (node (ref "IC6") (pin "4") (pinfunction "V-_4") (pintype "power_in"))
      (node (ref "IC7") (pin "10") (pinfunction "GNDR_10") (pintype "bidirectional"))
      (node (ref "IC7") (pin "12") (pinfunction "GND_12") (pintype "bidirectional"))
      (node (ref "IC7") (pin "13") (pinfunction "GND_13") (pintype "bidirectional"))
      (node (ref "IC7") (pin "16") (pinfunction "GND_16") (pintype "bidirectional"))
      (node (ref "IC7") (pin "5") (pinfunction "GND_5") (pintype "bidirectional"))
      (node (ref "IC7") (pin "7") (pinfunction "SA0/SDO_7") (pintype "bidirectional"))
      (node (ref "JP1") (pin "GND") (pinfunction "GND_GND") (pintype "bidirectional"))
      (node (ref "JP2") (pin "1") (pinfunction "1_1") (pintype "passive"))
      (node (ref "JP3") (pin "1") (pinfunction "1_1") (pintype "passive"))
      (node (ref "JP4") (pin "4") (pinfunction "4_4") (pintype "bidirectional"))
      (node (ref "JP6") (pin "1") (pinfunction "1_1") (pintype "passive"))
      (node (ref "JP7") (pin "1") (pinfunction "1_1") (pintype "passive"))
      (node (ref "JP8") (pin "3") (pinfunction "3_3") (pintype "passive"))
      (node (ref "M1") (pin "3") (pinfunction "S_3") (pintype "passive"))
      (node (ref "M2") (pin "3") (pinfunction "S_3") (pintype "passive"))
      (node (ref "M3") (pin "3") (pinfunction "S_3") (pintype "passive"))
      (node (ref "M4") (pin "3") (pinfunction "S_3") (pintype "passive"))
      (node (ref "Q1") (pin "2") (pinfunction "E_2") (pintype "passive"))
      (node (ref "Q2") (pin "2") (pinfunction "E_2") (pintype "passive"))
      (node (ref "Q3") (pin "2") (pinfunction "E_2") (pintype "passive"))
      (node (ref "Q4") (pin "2") (pinfunction "E_2") (pintype "passive"))
      (node (ref "Q5") (pin "2") (pinfunction "E_2") (pintype "passive"))
      (node (ref "Q6") (pin "2") (pinfunction "E_2") (pintype "passive"))
      (node (ref "Q7") (pin "2") (pinfunction "E_2") (pintype "passive"))
      (node (ref "Q8") (pin "2") (pinfunction "E_2") (pintype "passive"))
      (node (ref "Q9") (pin "2") (pinfunction "E_2") (pintype "passive"))
      (node (ref "R14") (pin "2") (pinfunction "2_2") (pintype "passive"))
      (node (ref "R15") (pin "1") (pinfunction "1_1") (pintype "passive"))
      (node (ref "R25") (pin "2") (pinfunction "2_2") (pintype "passive"))
      (node (ref "R31") (pin "1") (pinfunction "1_1") (pintype "passive"))
      (node (ref "R38") (pin "2") (pinfunction "2_2") (pintype "passive"))
      (node (ref "R9") (pin "1") (pinfunction "1_1") (pintype "passive"))
      (node (ref "S1") (pin "B2") (pinfunction "2_B2") (pintype "passive"))
      (node (ref "S2") (pin "B2") (pinfunction "2_B2") (pintype "passive"))
      (node (ref "S3") (pin "B2") (pinfunction "2_B2") (pintype "passive"))
      (node (ref "U$1") (pin "10") (pinfunction "BS0_10") (pintype "input"))
      (node (ref "U$1") (pin "11") (pinfunction "BS1_11") (pintype "input"))
      (node (ref "U$1") (pin "12") (pinfunction "BS2_12") (pintype "input"))
      (node (ref "U$1") (pin "16") (pinfunction "R/W_16") (pintype "input"))
      (node (ref "U$1") (pin "29") (pinfunction "VLSS_29") (pintype "power_in"))
      (node (ref "U$1") (pin "8") (pinfunction "VSS_8") (pintype "power_in"))
      (node (ref "ZD1") (pin "2") (pinfunction "A_2") (pintype "passive"))
      (node (ref "ZD2") (pin "2") (pinfunction "A_2") (pintype "passive"))
      (node (ref "ZD3") (pin "2") (pinfunction "A_2") (pintype "passive"))
      (node (ref "ZD4") (pin "2") (pinfunction "A_2") (pintype "passive"))
    )
    (net (code "51") (name "Net-(C23-Pad2)") (class "Default")
      (node (ref "C23") (pin "2") (pinfunction "2_2") (pintype "passive"))
      (node (ref "R18") (pin "1") (pinfunction "1_1") (pintype "passive"))
      (node (ref "R19") (pin "1") (pinfunction "1_1") (pintype "passive"))
    )
    (net (code "52") (name "Net-(D2-A)") (class "Default")
      (node (ref "D2") (pin "2") (pinfunction "A_2") (pintype "passive"))
      (node (ref "IC6") (pin "5") (pinfunction "+IN_5") (pintype "input"))
      (node (ref "R30") (pin "1") (pinfunction "1_1") (pintype "passive"))
      (node (ref "R31") (pin "2") (pinfunction "2_2") (pintype "passive"))
    )
    (net (code "53") (name "Net-(D3-A)") (class "Default")
      (node (ref "D3") (pin "2") (pinfunction "A_2") (pintype "passive"))
      (node (ref "IC6") (pin "3") (pinfunction "+IN_3") (pintype "input"))
      (node (ref "R32") (pin "2") (pinfunction "2_2") (pintype "passive"))
    )
    (net (code "54") (name "Net-(IC1-PA6)") (class "Default")
      (node (ref "IC1") (pin "16") (pinfunction "PA6_16") (pintype "bidirectional"))
      (node (ref "R24") (pin "2") (pinfunction "2_2") (pintype "passive"))
    )
    (net (code "55") (name "Net-(IC1-PA7)") (class "Default")
      (node (ref "IC1") (pin "17") (pinfunction "PA7_17") (pintype "bidirectional"))
      (node (ref "R23") (pin "2") (pinfunction "2_2") (pintype "passive"))
    )
    (net (code "56") (name "Net-(IC1-PB0)") (class "Default")
      (node (ref "IC1") (pin "18") (pinfunction "PB0_18") (pintype "bidirectional"))
      (node (ref "R22") (pin "2") (pinfunction "2_2") (pintype "passive"))
    )
    (net (code "57") (name "Net-(IC1-PB1)") (class "Default")
      (node (ref "IC1") (pin "19") (pinfunction "PB1_19") (pintype "bidirectional"))
      (node (ref "R21") (pin "2") (pinfunction "2_2") (pintype "passive"))
    )
    (net (code "58") (name "Net-(IC2-VFG)") (class "Default")
      (node (ref "IC2") (pin "1") (pinfunction "VFG_1") (pintype "bidirectional"))
      (node (ref "IC3") (pin "6") (pinfunction "P0W_6") (pintype "bidirectional"))
    )
    (net (code "59") (name "Net-(IC2-VREF)") (class "Default")
      (node (ref "IC2") (pin "5") (pinfunction "VREF_5") (pintype "bidirectional"))
      (node (ref "IC3") (pin "5") (pinfunction "P0A_5") (pintype "bidirectional"))
      (node (ref "R10") (pin "2") (pinfunction "2_2") (pintype "passive"))
      (node (ref "R9") (pin "2") (pinfunction "2_2") (pintype "passive"))
    )
    (net (code "60") (name "Net-(IC3-P0B)") (class "Default")
      (node (ref "IC3") (pin "7") (pinfunction "P0B_7") (pintype "bidirectional"))
      (node (ref "R11") (pin "2") (pinfunction "2_2") (pintype "passive"))
    )
    (net (code "61") (name "Net-(IC5-USBDM)") (class "Default")
      (node (ref "IC5") (pin "9") (pinfunction "USBDM_9") (pintype "input"))
      (node (ref "R16") (pin "2") (pinfunction "2_2") (pintype "passive"))
    )
    (net (code "62") (name "Net-(IC5-USBDP)") (class "Default")
      (node (ref "IC5") (pin "8") (pinfunction "USBDP_8") (pintype "input"))
      (node (ref "R17") (pin "1") (pinfunction "1_1") (pintype "passive"))
    )
    (net (code "63") (name "Net-(IC6A--IN)") (class "Default")
      (node (ref "IC6") (pin "1") (pinfunction "OUT_1") (pintype "output"))
      (node (ref "IC6") (pin "2") (pinfunction "-IN_2") (pintype "input"))
      (node (ref "R34") (pin "1") (pinfunction "1_1") (pintype "passive"))
    )
    (net (code "64") (name "Net-(IC6B--IN)") (class "Default")
      (node (ref "IC6") (pin "6") (pinfunction "-IN_6") (pintype "input"))
      (node (ref "IC6") (pin "7") (pinfunction "OUT_7") (pintype "output"))
      (node (ref "R33") (pin "1") (pinfunction "1_1") (pintype "passive"))
    )
    (net (code "65") (name "Net-(JP2-Pad2)") (class "Default")
      (node (ref "JP2") (pin "2") (pinfunction "2_2") (pintype "passive"))
      (node (ref "R28") (pin "1") (pinfunction "1_1") (pintype "passive"))
    )
    (net (code "66") (name "Net-(JP3-Pad2)") (class "Default")
      (node (ref "JP3") (pin "2") (pinfunction "2_2") (pintype "passive"))
      (node (ref "R26") (pin "1") (pinfunction "1_1") (pintype "passive"))
    )
    (net (code "67") (name "Net-(JP7-Pad2)") (class "Default")
      (node (ref "JP7") (pin "2") (pinfunction "2_2") (pintype "passive"))
      (node (ref "R36") (pin "1") (pinfunction "1_1") (pintype "passive"))
    )
    (net (code "68") (name "Net-(JP7-Pad3)") (class "Default")
      (node (ref "JP7") (pin "3") (pinfunction "3_3") (pintype "passive"))
      (node (ref "R32") (pin "1") (pinfunction "1_1") (pintype "passive"))
    )
    (net (code "69") (name "Net-(M1-D)") (class "Default")
      (node (ref "C3") (pin "2") (pinfunction "2_2") (pintype "passive"))
      (node (ref "C4") (pin "2") (pinfunction "2_2") (pintype "passive"))
      (node (ref "M1") (pin "4") (pinfunction "D_4") (pintype "passive"))
    )
    (net (code "70") (name "Net-(M1-G)") (class "Default")
      (node (ref "M1") (pin "1") (pinfunction "G_1") (pintype "passive"))
      (node (ref "R2") (pin "1") (pinfunction "1_1") (pintype "passive"))
      (node (ref "ZD1") (pin "1") (pinfunction "C_1") (pintype "passive"))
    )
    (net (code "71") (name "Net-(M2-D)") (class "Default")
      (node (ref "C5") (pin "2") (pinfunction "2_2") (pintype "passive"))
      (node (ref "C6") (pin "2") (pinfunction "2_2") (pintype "passive"))
      (node (ref "M2") (pin "4") (pinfunction "D_4") (pintype "passive"))
    )
    (net (code "72") (name "Net-(M2-G)") (class "Default")
      (node (ref "M2") (pin "1") (pinfunction "G_1") (pintype "passive"))
      (node (ref "R4") (pin "1") (pinfunction "1_1") (pintype "passive"))
      (node (ref "ZD2") (pin "1") (pinfunction "C_1") (pintype "passive"))
    )
    (net (code "73") (name "Net-(M3-D)") (class "Default")
      (node (ref "C7") (pin "2") (pinfunction "2_2") (pintype "passive"))
      (node (ref "C8") (pin "2") (pinfunction "2_2") (pintype "passive"))
      (node (ref "M3") (pin "4") (pinfunction "D_4") (pintype "passive"))
    )
    (net (code "74") (name "Net-(M3-G)") (class "Default")
      (node (ref "M3") (pin "1") (pinfunction "G_1") (pintype "passive"))
      (node (ref "R6") (pin "1") (pinfunction "1_1") (pintype "passive"))
      (node (ref "ZD3") (pin "1") (pinfunction "C_1") (pintype "passive"))
    )
    (net (code "75") (name "Net-(M4-D)") (class "Default")
      (node (ref "C10") (pin "2") (pinfunction "2_2") (pintype "passive"))
      (node (ref "C9") (pin "2") (pinfunction "2_2") (pintype "passive"))
      (node (ref "M4") (pin "4") (pinfunction "D_4") (pintype "passive"))
    )
    (net (code "76") (name "Net-(M4-G)") (class "Default")
      (node (ref "M4") (pin "1") (pinfunction "G_1") (pintype "passive"))
      (node (ref "R8") (pin "1") (pinfunction "1_1") (pintype "passive"))
      (node (ref "ZD4") (pin "1") (pinfunction "C_1") (pintype "passive"))
    )
    (net (code "77") (name "Net-(Q1-C)") (class "Default")
      (node (ref "Q1") (pin "3") (pinfunction "C_3") (pintype "passive"))
      (node (ref "R1") (pin "1") (pinfunction "1_1") (pintype "passive"))
      (node (ref "R2") (pin "2") (pinfunction "2_2") (pintype "passive"))
    )
    (net (code "78") (name "Net-(Q2-C)") (class "Default")
      (node (ref "Q2") (pin "3") (pinfunction "C_3") (pintype "passive"))
      (node (ref "R3") (pin "1") (pinfunction "1_1") (pintype "passive"))
      (node (ref "R4") (pin "2") (pinfunction "2_2") (pintype "passive"))
    )
    (net (code "79") (name "Net-(Q3-C)") (class "Default")
      (node (ref "Q3") (pin "3") (pinfunction "C_3") (pintype "passive"))
      (node (ref "R5") (pin "1") (pinfunction "1_1") (pintype "passive"))
      (node (ref "R6") (pin "2") (pinfunction "2_2") (pintype "passive"))
    )
    (net (code "80") (name "Net-(Q4-C)") (class "Default")
      (node (ref "Q4") (pin "3") (pinfunction "C_3") (pintype "passive"))
      (node (ref "R7") (pin "1") (pinfunction "1_1") (pintype "passive"))
      (node (ref "R8") (pin "2") (pinfunction "2_2") (pintype "passive"))
    )
    (net (code "81") (name "Net-(Q5-B)") (class "Default")
      (node (ref "Q5") (pin "1") (pinfunction "B_1") (pintype "passive"))
      (node (ref "R26") (pin "2") (pinfunction "2_2") (pintype "passive"))
    )
    (net (code "82") (name "Net-(Q6-B)") (class "Default")
      (node (ref "Q6") (pin "1") (pinfunction "B_1") (pintype "passive"))
      (node (ref "R28") (pin "2") (pinfunction "2_2") (pintype "passive"))
    )
    (net (code "83") (name "Net-(Q7-B)") (class "Default")
      (node (ref "Q7") (pin "1") (pinfunction "B_1") (pintype "passive"))
      (node (ref "R29") (pin "1") (pinfunction "1_1") (pintype "passive"))
    )
    (net (code "84") (name "Net-(Q7-C)") (class "Default")
      (node (ref "Q7") (pin "3") (pinfunction "C_3") (pintype "passive"))
      (node (ref "R36") (pin "2") (pinfunction "2_2") (pintype "passive"))
    )
    (net (code "85") (name "Net-(Q8-B)") (class "Default")
      (node (ref "C32") (pin "1") (pinfunction "1_1") (pintype "passive"))
      (node (ref "Q8") (pin "1") (pinfunction "B_1") (pintype "passive"))
      (node (ref "R37") (pin "1") (pinfunction "1_1") (pintype "passive"))
      (node (ref "R38") (pin "1") (pinfunction "1_1") (pintype "passive"))
    )
    (net (code "86") (name "Net-(Q9-B)") (class "Default")
      (node (ref "Q9") (pin "1") (pinfunction "B_1") (pintype "passive"))
      (node (ref "R39") (pin "1") (pinfunction "1_1") (pintype "passive"))
    )
    (net (code "87") (name "Net-(U$1-C1N)") (class "Default")
      (node (ref "C12") (pin "1") (pinfunction "1_1") (pintype "passive"))
      (node (ref "U$1") (pin "5") (pinfunction "C1N_5") (pintype "input"))
    )
    (net (code "88") (name "Net-(U$1-C1P)") (class "Default")
      (node (ref "C12") (pin "2") (pinfunction "2_2") (pintype "passive"))
      (node (ref "U$1") (pin "4") (pinfunction "C1P_4") (pintype "input"))
    )
    (net (code "89") (name "Net-(U$1-C2N)") (class "Default")
      (node (ref "C11") (pin "1") (pinfunction "1_1") (pintype "passive"))
      (node (ref "U$1") (pin "3") (pinfunction "C2N_3") (pintype "input"))
    )
    (net (code "90") (name "Net-(U$1-C2P)") (class "Default")
      (node (ref "C11") (pin "2") (pinfunction "2_2") (pintype "passive"))
      (node (ref "U$1") (pin "2") (pinfunction "C2P_2") (pintype "input"))
    )
    (net (code "91") (name "Net-(U$1-IREF)") (class "Default")
      (node (ref "R15") (pin "2") (pinfunction "2_2") (pintype "passive"))
      (node (ref "U$1") (pin "26") (pinfunction "IREF_26") (pintype "input"))
    )
    (net (code "92") (name "VCC") (class "Default")
      (node (ref "C1") (pin "1") (pinfunction "1_1") (pintype "passive"))
      (node (ref "D1") (pin "C") (pinfunction "C_C") (pintype "passive"))
      (node (ref "D4") (pin "C") (pinfunction "C_C") (pintype "passive"))
      (node (ref "IC4") (pin "3") (pinfunction "IN_3") (pintype "input"))
      (node (ref "JP2") (pin "3") (pinfunction "3_3") (pintype "passive"))
      (node (ref "JP3") (pin "3") (pinfunction "3_3") (pintype "passive"))
      (node (ref "JP7") (pin "4") (pinfunction "4_4") (pintype "passive"))
      (node (ref "R1") (pin "2") (pinfunction "2_2") (pintype "passive"))
      (node (ref "R3") (pin "2") (pinfunction "2_2") (pintype "passive"))
      (node (ref "R30") (pin "2") (pinfunction "2_2") (pintype "passive"))
      (node (ref "R5") (pin "2") (pinfunction "2_2") (pintype "passive"))
      (node (ref "R7") (pin "2") (pinfunction "2_2") (pintype "passive"))
    )
    (net (code "93") (name "unconnected-(IC1-PA3-Pad13)") (class "Default")
      (node (ref "IC1") (pin "13") (pinfunction "PA3_13") (pintype "bidirectional"))
    )
    (net (code "94") (name "unconnected-(IC1-PA4-Pad14)") (class "Default")
      (node (ref "IC1") (pin "14") (pinfunction "PA4_14") (pintype "bidirectional"))
    )
    (net (code "95") (name "unconnected-(IC1-PA5-Pad15)") (class "Default")
      (node (ref "IC1") (pin "15") (pinfunction "PA5_15") (pintype "bidirectional"))
    )
    (net (code "96") (name "unconnected-(IC1-PA8-Pad29)") (class "Default")
      (node (ref "IC1") (pin "29") (pinfunction "PA8_29") (pintype "bidirectional"))
    )
    (net (code "97") (name "unconnected-(IC1-PA12-Pad33)") (class "Default")
      (node (ref "IC1") (pin "33") (pinfunction "PA12_33") (pintype "bidirectional"))
    )
    (net (code "98") (name "unconnected-(IC1-PB2-Pad20)") (class "Default")
      (node (ref "IC1") (pin "20") (pinfunction "PB2_20") (pintype "bidirectional"))
    )
    (net (code "99") (name "unconnected-(IC1-PB14-Pad27)") (class "Default")
      (node (ref "IC1") (pin "27") (pinfunction "PB14_27") (pintype "bidirectional"))
    )
    (net (code "100") (name "unconnected-(IC1-PB15-Pad28)") (class "Default")
      (node (ref "IC1") (pin "28") (pinfunction "PB15_28") (pintype "bidirectional"))
    )
    (net (code "101") (name "unconnected-(IC1-PF1-Pad6)") (class "Default")
      (node (ref "IC1") (pin "6") (pinfunction "PF1_6") (pintype "bidirectional"))
    )
    (net (code "102") (name "unconnected-(IC1-PF6-Pad35)") (class "Default")
      (node (ref "IC1") (pin "35") (pinfunction "PF6_35") (pintype "bidirectional"))
    )
    (net (code "103") (name "unconnected-(IC1-PF7-Pad36)") (class "Default")
      (node (ref "IC1") (pin "36") (pinfunction "PF7_36") (pintype "bidirectional"))
    )
    (net (code "104") (name "unconnected-(IC5-~{CTS}-Pad6)") (class "Default")
      (node (ref "IC5") (pin "6") (pinfunction "~{CTS}_6") (pintype "input"))
    )
    (net (code "105") (name "unconnected-(IC5-~{RTS}-Pad2)") (class "Default")
      (node (ref "IC5") (pin "2") (pinfunction "~{RTS}_2") (pintype "output"))
    )
    (net (code "106") (name "unconnected-(JP4-Pad5)") (class "Default")
      (node (ref "JP4") (pin "5") (pinfunction "5_5") (pintype "bidirectional"))
    )
    (net (code "107") (name "unconnected-(U$1-D2-Pad20)") (class "Default")
      (node (ref "U$1") (pin "20") (pinfunction "D2_20") (pintype "bidirectional"))
    )
    (net (code "108") (name "unconnected-(U$1-D3-Pad21)") (class "Default")
      (node (ref "U$1") (pin "21") (pinfunction "D3_21") (pintype "bidirectional"))
    )
    (net (code "109") (name "unconnected-(U$1-D4-Pad22)") (class "Default")
      (node (ref "U$1") (pin "22") (pinfunction "D4_22") (pintype "bidirectional"))
    )
    (net (code "110") (name "unconnected-(U$1-D5-Pad23)") (class "Default")
      (node (ref "U$1") (pin "23") (pinfunction "D5_23") (pintype "bidirectional"))
    )
    (net (code "111") (name "unconnected-(U$1-D6-Pad24)") (class "Default")
      (node (ref "U$1") (pin "24") (pinfunction "D6_24") (pintype "bidirectional"))
    )
    (net (code "112") (name "unconnected-(U$1-D7-Pad25)") (class "Default")
      (node (ref "U$1") (pin "25") (pinfunction "D7_25") (pintype "bidirectional"))
    )
    (net (code "113") (name "unconnected-(U$1-E{slash}RD-Pad17)") (class "Default")
      (node (ref "U$1") (pin "17") (pinfunction "E/RD_17") (pintype "input"))
    )
    (net (code "114") (name "unconnected-(U$1-MT-Pad1)") (class "Default")
      (node (ref "U$1") (pin "1") (pinfunction "MT_1") (pintype "input"))
    )
    (net (code "115") (name "unconnected-(U$1-MT2-Pad30)") (class "Default")
      (node (ref "U$1") (pin "30") (pinfunction "MT2_30") (pintype "input"))
    )
    (net (code "116") (name "unconnected-(U$1-NC-Pad7)") (class "Default")
      (node (ref "U$1") (pin "7") (pinfunction "NC_7") (pintype "no_connect"))
    )
  )
)
